# LEDdriverSFE.net
KiCad netlist of a schematic drawn in EAGLE
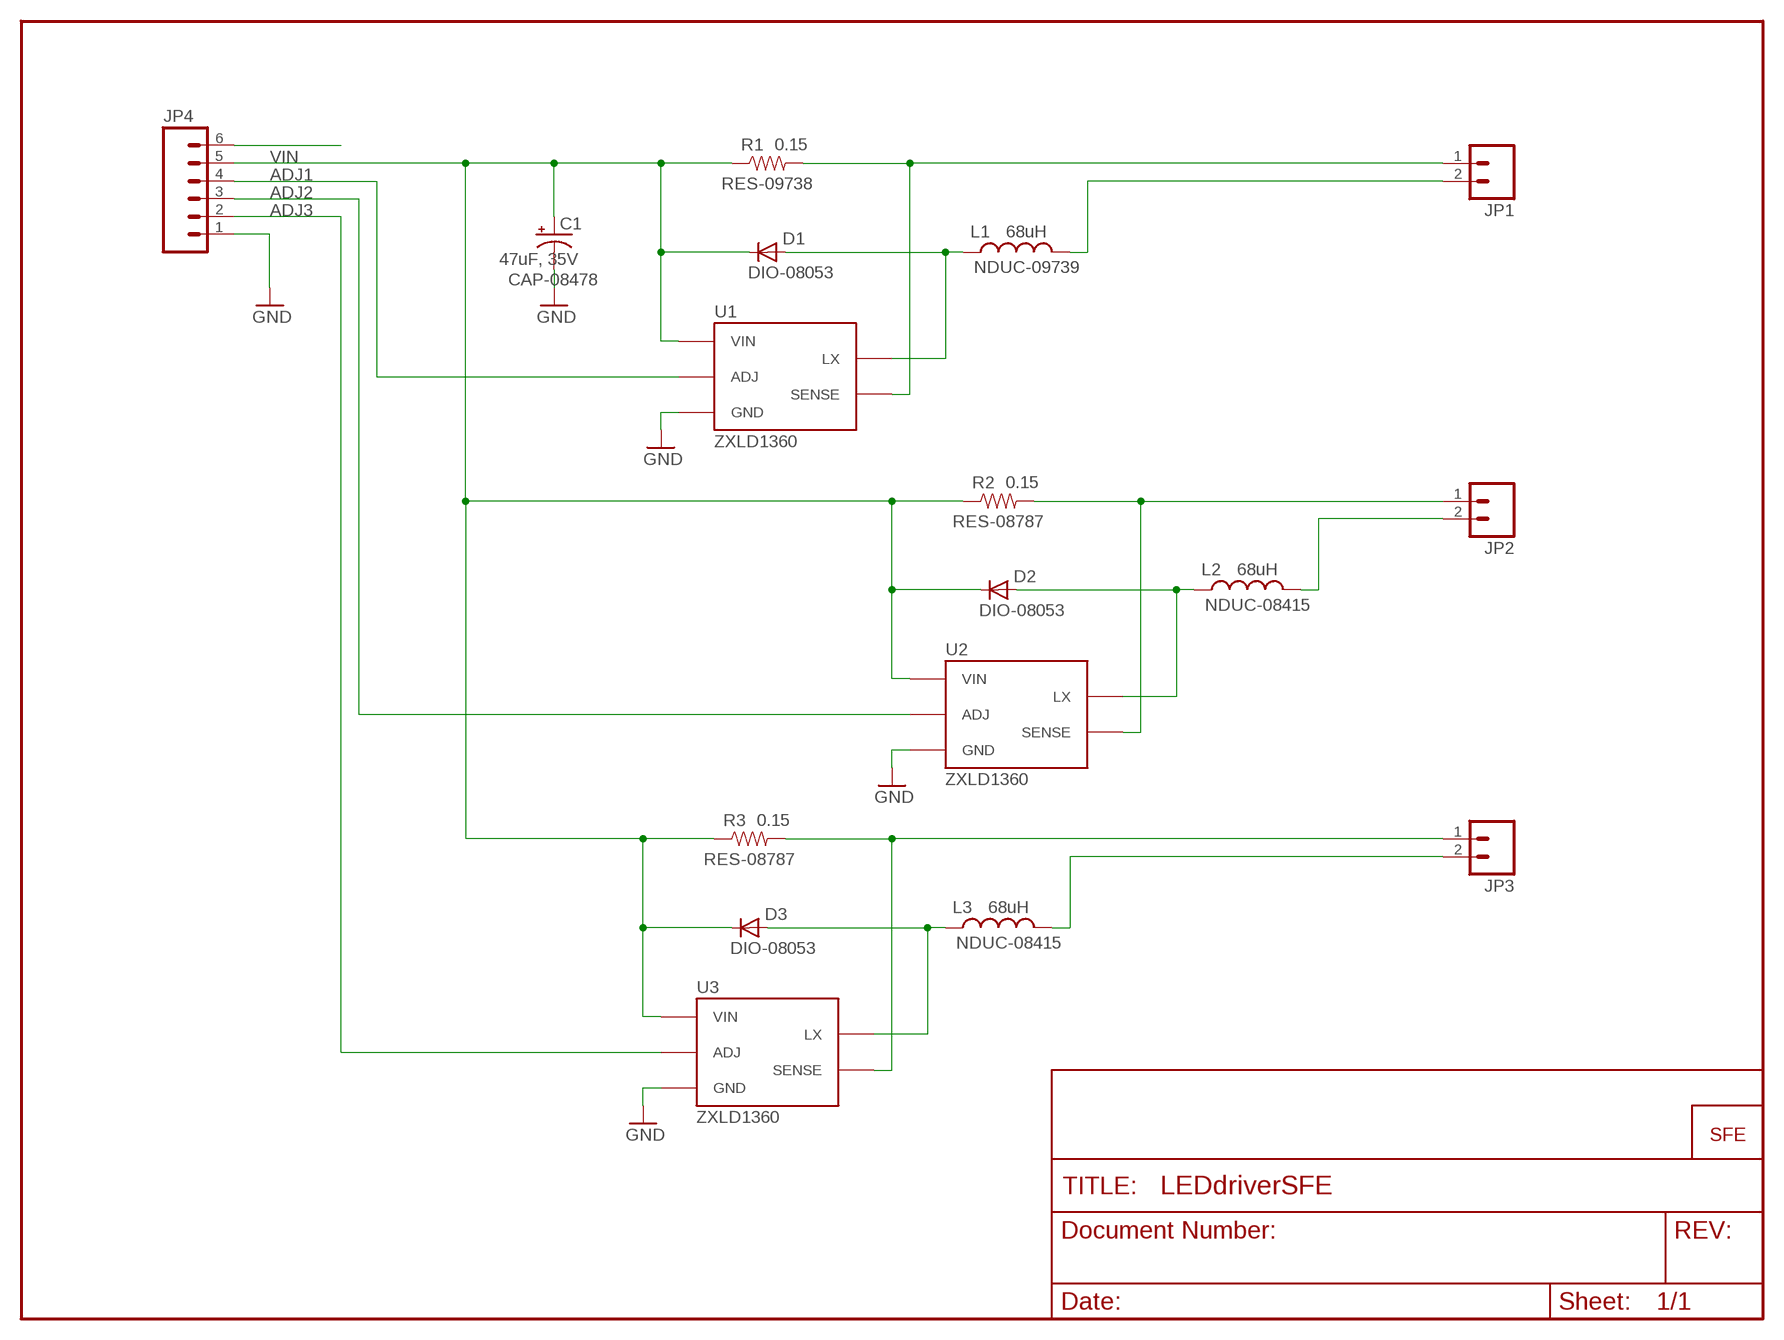
[diagram p0: schematic, sheet 1]

(export (version "E")
  (design (tool "Eeschema 10.0.6"))
  (components
    (comp (ref "C1")
      (value "47uF, 35V")
      (footprint "eagle-import:PANASONIC_D")
      (libsource (lib "eagle-import") (part "CAP_POLD"))
    )
    (comp (ref "D1")
      (value "MBRA140")
      (footprint "eagle-import:SMA-DIODE")
      (libsource (lib "eagle-import") (part "DIODESMA"))
    )
    (comp (ref "D2")
      (value "MBRA140")
      (footprint "eagle-import:SMA-DIODE")
      (libsource (lib "eagle-import") (part "DIODESMA"))
    )
    (comp (ref "D3")
      (value "MBRA140")
      (footprint "eagle-import:SMA-DIODE")
      (libsource (lib "eagle-import") (part "DIODESMA"))
    )
    (comp (ref "JP1")
      (value "M02")
      (footprint "eagle-import:1X02_LONGPADS")
      (libsource (lib "eagle-import") (part "M02"))
    )
    (comp (ref "JP2")
      (value "M02")
      (footprint "eagle-import:1X02_LONGPADS")
      (libsource (lib "eagle-import") (part "M02"))
    )
    (comp (ref "JP3")
      (value "M02")
      (footprint "eagle-import:1X02_LONGPADS")
      (libsource (lib "eagle-import") (part "M02"))
    )
    (comp (ref "JP4")
      (value "M06SIP")
      (footprint "eagle-import:1X06")
      (libsource (lib "eagle-import") (part "M06SIP"))
    )
    (comp (ref "JP5")
      (value "LOGO-SFENEW")
      (footprint "eagle-import:SFE-NEW-WEBLOGO")
      (libsource (lib "eagle-import") (part "LOGO-SFENEW"))
    )
    (comp (ref "L1")
      (value "68uH")
      (footprint "eagle-import:CR75")
      (libsource (lib "eagle-import") (part "INDUCTORCR75"))
    )
    (comp (ref "L2")
      (value "68uH")
      (footprint "eagle-import:CR75")
      (libsource (lib "eagle-import") (part "INDUCTORCR75"))
    )
    (comp (ref "L3")
      (value "68uH")
      (footprint "eagle-import:CR75")
      (libsource (lib "eagle-import") (part "INDUCTORCR75"))
    )
    (comp (ref "R1")
      (value "0.15")
      (footprint "eagle-import:0603-RES")
      (libsource (lib "eagle-import") (part "RESISTOR0603-RES"))
    )
    (comp (ref "R2")
      (value "0.15")
      (footprint "eagle-import:0603-RES")
      (libsource (lib "eagle-import") (part "RESISTOR0603-RES"))
    )
    (comp (ref "R3")
      (value "0.15")
      (footprint "eagle-import:0603-RES")
      (libsource (lib "eagle-import") (part "RESISTOR0603-RES"))
    )
    (comp (ref "U1")
      (value "ZXLD1360")
      (footprint "eagle-import:SOT23-5")
      (libsource (lib "eagle-import") (part "ZXLD1360"))
    )
    (comp (ref "U2")
      (value "ZXLD1360")
      (footprint "eagle-import:SOT23-5")
      (libsource (lib "eagle-import") (part "ZXLD1360"))
    )
    (comp (ref "U3")
      (value "ZXLD1360")
      (footprint "eagle-import:SOT23-5")
      (libsource (lib "eagle-import") (part "ZXLD1360"))
    )
  )
  (nets
    (net (code "1") (name "/ADJ1") (class "Default")
      (node (ref "JP4") (pin "4") (pinfunction "4_4") (pintype "passive"))
      (node (ref "U1") (pin "3") (pinfunction "ADJ_3") (pintype "bidirectional"))
    )
    (net (code "2") (name "/ADJ2") (class "Default")
      (node (ref "JP4") (pin "3") (pinfunction "3_3") (pintype "passive"))
      (node (ref "U2") (pin "3") (pinfunction "ADJ_3") (pintype "bidirectional"))
    )
    (net (code "3") (name "/ADJ3") (class "Default")
      (node (ref "JP4") (pin "2") (pinfunction "2_2") (pintype "passive"))
      (node (ref "U3") (pin "3") (pinfunction "ADJ_3") (pintype "bidirectional"))
    )
    (net (code "4") (name "/VIN") (class "Default")
      (node (ref "C1") (pin "+") (pinfunction "+_+") (pintype "passive"))
      (node (ref "D1") (pin "C") (pinfunction "C_C") (pintype "passive"))
      (node (ref "D2") (pin "C") (pinfunction "C_C") (pintype "passive"))
      (node (ref "D3") (pin "C") (pinfunction "C_C") (pintype "passive"))
      (node (ref "JP4") (pin "5") (pinfunction "5_5") (pintype "passive"))
      (node (ref "R1") (pin "1") (pinfunction "1_1") (pintype "passive"))
      (node (ref "R2") (pin "1") (pinfunction "1_1") (pintype "passive"))
      (node (ref "R3") (pin "1") (pinfunction "1_1") (pintype "passive"))
      (node (ref "U1") (pin "5") (pinfunction "VIN_5") (pintype "bidirectional"))
      (node (ref "U2") (pin "5") (pinfunction "VIN_5") (pintype "bidirectional"))
      (node (ref "U3") (pin "5") (pinfunction "VIN_5") (pintype "bidirectional"))
    )
    (net (code "5") (name "GND") (class "Default")
      (node (ref "C1") (pin "-") (pinfunction "-_-") (pintype "passive"))
      (node (ref "JP4") (pin "1") (pinfunction "1_1") (pintype "passive"))
      (node (ref "U1") (pin "2") (pinfunction "GND_2") (pintype "bidirectional"))
      (node (ref "U2") (pin "2") (pinfunction "GND_2") (pintype "bidirectional"))
      (node (ref "U3") (pin "2") (pinfunction "GND_2") (pintype "bidirectional"))
    )
    (net (code "6") (name "Net-(L1-1)") (class "Default")
      (node (ref "D1") (pin "A") (pinfunction "A_A") (pintype "passive"))
      (node (ref "L1") (pin "P$1") (pinfunction "1_P$1") (pintype "passive"))
      (node (ref "U1") (pin "1") (pinfunction "LX_1") (pintype "bidirectional"))
    )
    (net (code "7") (name "Net-(L1-2)") (class "Default")
      (node (ref "JP1") (pin "2") (pinfunction "2_2") (pintype "passive"))
      (node (ref "L1") (pin "P$2") (pinfunction "2_P$2") (pintype "passive"))
    )
    (net (code "8") (name "Net-(L2-1)") (class "Default")
      (node (ref "D2") (pin "A") (pinfunction "A_A") (pintype "passive"))
      (node (ref "L2") (pin "P$1") (pinfunction "1_P$1") (pintype "passive"))
      (node (ref "U2") (pin "1") (pinfunction "LX_1") (pintype "bidirectional"))
    )
    (net (code "9") (name "Net-(L2-2)") (class "Default")
      (node (ref "JP2") (pin "2") (pinfunction "2_2") (pintype "passive"))
      (node (ref "L2") (pin "P$2") (pinfunction "2_P$2") (pintype "passive"))
    )
    (net (code "10") (name "Net-(L3-1)") (class "Default")
      (node (ref "D3") (pin "A") (pinfunction "A_A") (pintype "passive"))
      (node (ref "L3") (pin "P$1") (pinfunction "1_P$1") (pintype "passive"))
      (node (ref "U3") (pin "1") (pinfunction "LX_1") (pintype "bidirectional"))
    )
    (net (code "11") (name "Net-(L3-2)") (class "Default")
      (node (ref "JP3") (pin "2") (pinfunction "2_2") (pintype "passive"))
      (node (ref "L3") (pin "P$2") (pinfunction "2_P$2") (pintype "passive"))
    )
    (net (code "12") (name "Net-(U1-SENSE)") (class "Default")
      (node (ref "JP1") (pin "1") (pinfunction "1_1") (pintype "passive"))
      (node (ref "R1") (pin "2") (pinfunction "2_2") (pintype "passive"))
      (node (ref "U1") (pin "4") (pinfunction "SENSE_4") (pintype "bidirectional"))
    )
    (net (code "13") (name "Net-(U2-SENSE)") (class "Default")
      (node (ref "JP2") (pin "1") (pinfunction "1_1") (pintype "passive"))
      (node (ref "R2") (pin "2") (pinfunction "2_2") (pintype "passive"))
      (node (ref "U2") (pin "4") (pinfunction "SENSE_4") (pintype "bidirectional"))
    )
    (net (code "14") (name "Net-(U3-SENSE)") (class "Default")
      (node (ref "JP3") (pin "1") (pinfunction "1_1") (pintype "passive"))
      (node (ref "R3") (pin "2") (pinfunction "2_2") (pintype "passive"))
      (node (ref "U3") (pin "4") (pinfunction "SENSE_4") (pintype "bidirectional"))
    )
    (net (code "15") (name "unconnected-(JP4-Pad6)") (class "Default")
      (node (ref "JP4") (pin "6") (pinfunction "6_6") (pintype "passive"))
    )
  )
)
